# auto.net
KiCad netlist of a schematic drawn in EAGLE
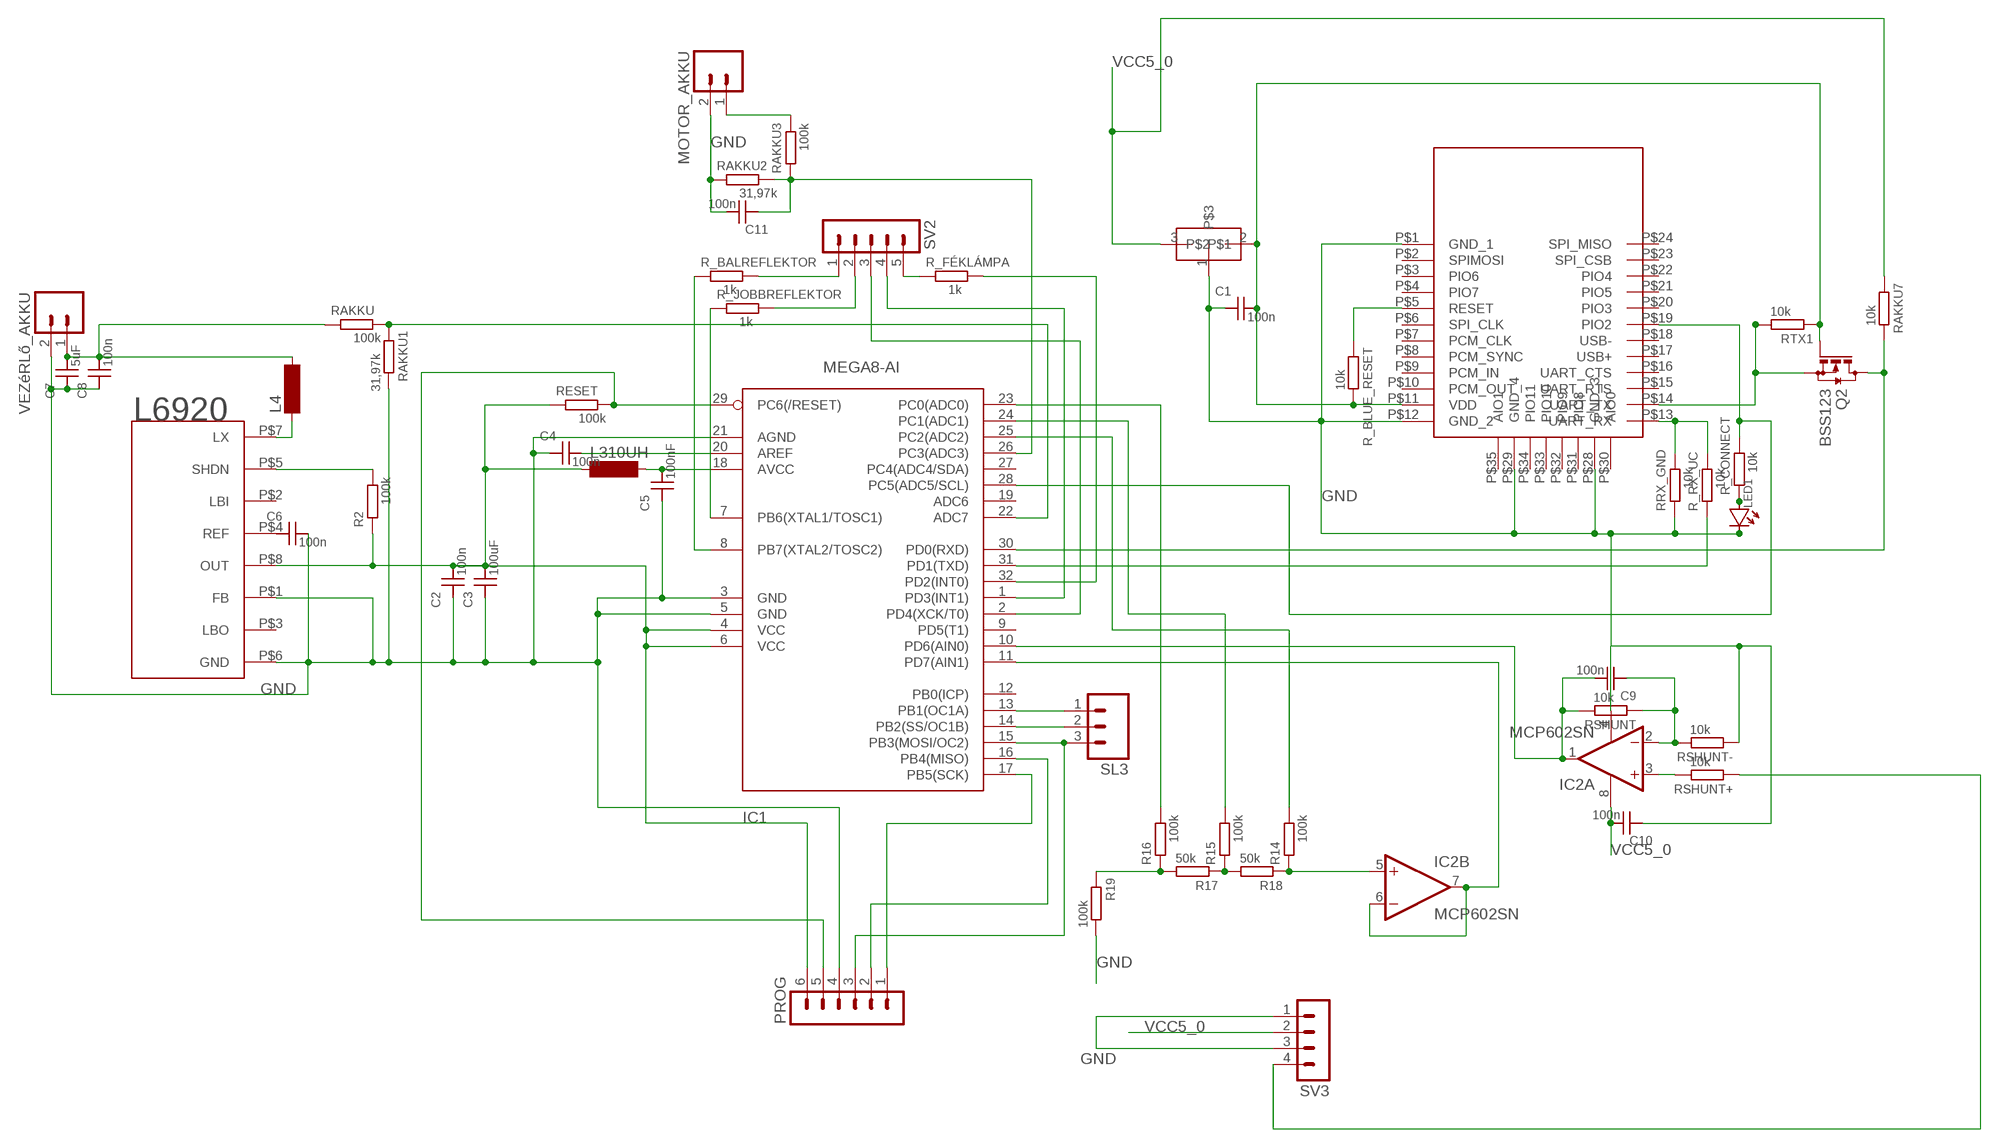
[diagram p0: schematic, sheet 1]

(export (version "E")
  (design (tool "Eeschema 10.0.6"))
  (components
    (comp (ref "C1")
      (value "100n")
      (footprint "eagle-import:1206")
      (libsource (lib "eagle-import") (part "C"))
    )
    (comp (ref "C2")
      (value "100n")
      (footprint "eagle-import:1206")
      (libsource (lib "eagle-import") (part "C"))
    )
    (comp (ref "C3")
      (value "100uF")
      (footprint "eagle-import:1206")
      (libsource (lib "eagle-import") (part "C"))
    )
    (comp (ref "C4")
      (value "100n")
      (footprint "eagle-import:1206")
      (libsource (lib "eagle-import") (part "C"))
    )
    (comp (ref "C5")
      (value "100nF")
      (footprint "eagle-import:1206")
      (libsource (lib "eagle-import") (part "C"))
    )
    (comp (ref "C6")
      (value "100n")
      (footprint "eagle-import:1206")
      (libsource (lib "eagle-import") (part "C"))
    )
    (comp (ref "C7")
      (value "5uF")
      (footprint "eagle-import:1206")
      (libsource (lib "eagle-import") (part "C"))
    )
    (comp (ref "C8")
      (value "100n")
      (footprint "eagle-import:1206")
      (libsource (lib "eagle-import") (part "C"))
    )
    (comp (ref "C9")
      (value "100n")
      (footprint "eagle-import:1206")
      (libsource (lib "eagle-import") (part "C"))
    )
    (comp (ref "C10")
      (value "100n")
      (footprint "eagle-import:1206")
      (libsource (lib "eagle-import") (part "C"))
    )
    (comp (ref "C11")
      (value "100n")
      (footprint "eagle-import:1206")
      (libsource (lib "eagle-import") (part "C"))
    )
    (comp (ref "IC1")
      (value "MEGA8-AI")
      (footprint "eagle-import:TQFP32-08")
      (libsource (lib "eagle-import") (part "MEGA8-AI"))
    )
    (comp (ref "IC2")
      (value "MCP602SN")
      (footprint "eagle-import:SO08")
      (libsource (lib "eagle-import") (part "MCP602SN"))
    )
    (comp (ref "L4")
      (value "SM-NE29")
      (footprint "eagle-import:SM-NE29")
      (libsource (lib "eagle-import") (part "SM-NE29"))
    )
    (comp (ref "L310UH")
      (value "SM-NE29")
      (footprint "eagle-import:SM-NE29")
      (libsource (lib "eagle-import") (part "SM-NE29"))
    )
    (comp (ref "LED1")
      (value "LED")
      (footprint "eagle-import:1206")
      (libsource (lib "eagle-import") (part "LED"))
    )
    (comp (ref "MCP1700-3302")
      (value "MCP1700-1802")
      (footprint "eagle-import:SOT23")
      (libsource (lib "eagle-import") (part "MCP1700-1802"))
    )
    (comp (ref "MOTOR_AKKU")
      (value "M02")
      (footprint "eagle-import:02P")
      (fields (field (name "OC_FARNELL") "unknown") (field (name "OC_NEWARK") "unknown"))
      (libsource (lib "eagle-import") (part "M02"))
    )
    (comp (ref "PROG")
      (value "MA06-1")
      (footprint "eagle-import:MA06-1")
      (libsource (lib "eagle-import") (part "MA06-1"))
    )
    (comp (ref "Q2")
      (value "BSS123")
      (footprint "eagle-import:SOT23")
      (libsource (lib "eagle-import") (part "transistor-small-signal_BSS123"))
    )
    (comp (ref "R2")
      (value "100k")
      (footprint "eagle-import:1206")
      (libsource (lib "eagle-import") (part "R"))
    )
    (comp (ref "R14")
      (value "100k")
      (footprint "eagle-import:1206")
      (libsource (lib "eagle-import") (part "R"))
    )
    (comp (ref "R15")
      (value "100k")
      (footprint "eagle-import:1206")
      (libsource (lib "eagle-import") (part "R"))
    )
    (comp (ref "R16")
      (value "100k")
      (footprint "eagle-import:1206")
      (libsource (lib "eagle-import") (part "R"))
    )
    (comp (ref "R17")
      (value "50k")
      (footprint "eagle-import:1206")
      (libsource (lib "eagle-import") (part "R"))
    )
    (comp (ref "R18")
      (value "50k")
      (footprint "eagle-import:1206")
      (libsource (lib "eagle-import") (part "R"))
    )
    (comp (ref "R19")
      (value "100k")
      (footprint "eagle-import:1206")
      (libsource (lib "eagle-import") (part "R"))
    )
    (comp (ref "RAKKU")
      (value "100k")
      (footprint "eagle-import:1206")
      (libsource (lib "eagle-import") (part "R"))
    )
    (comp (ref "RAKKU1")
      (value "31,97k")
      (footprint "eagle-import:1206")
      (libsource (lib "eagle-import") (part "R"))
    )
    (comp (ref "RAKKU2")
      (value "31,97k")
      (footprint "eagle-import:1206")
      (libsource (lib "eagle-import") (part "R"))
    )
    (comp (ref "RAKKU3")
      (value "100k")
      (footprint "eagle-import:1206")
      (libsource (lib "eagle-import") (part "R"))
    )
    (comp (ref "RAKKU7")
      (value "10k")
      (footprint "eagle-import:1206")
      (libsource (lib "eagle-import") (part "R"))
    )
    (comp (ref "RESET")
      (value "100k")
      (footprint "eagle-import:1206")
      (libsource (lib "eagle-import") (part "R"))
    )
    (comp (ref "RRX_GND")
      (value "10k")
      (footprint "eagle-import:1206")
      (libsource (lib "eagle-import") (part "R"))
    )
    (comp (ref "RSHUNT")
      (value "10k")
      (footprint "eagle-import:1206")
      (libsource (lib "eagle-import") (part "R"))
    )
    (comp (ref "RSHUNT+")
      (value "10k")
      (footprint "eagle-import:1206")
      (libsource (lib "eagle-import") (part "R"))
    )
    (comp (ref "RSHUNT-")
      (value "10k")
      (footprint "eagle-import:1206")
      (libsource (lib "eagle-import") (part "R"))
    )
    (comp (ref "RTX1")
      (value "10k")
      (footprint "eagle-import:1206")
      (libsource (lib "eagle-import") (part "R"))
    )
    (comp (ref "R_BALREFLEKTOR")
      (value "1k")
      (footprint "eagle-import:1206")
      (libsource (lib "eagle-import") (part "R"))
    )
    (comp (ref "R_BLUE_RESET")
      (value "10k")
      (footprint "eagle-import:1206")
      (libsource (lib "eagle-import") (part "R"))
    )
    (comp (ref "R_CONNECT")
      (value "10k")
      (footprint "eagle-import:1206")
      (libsource (lib "eagle-import") (part "R"))
    )
    (comp (ref "R_FÉKLÁMPA")
      (value "1k")
      (footprint "eagle-import:1206")
      (libsource (lib "eagle-import") (part "R"))
    )
    (comp (ref "R_JOBBREFLEKTOR")
      (value "1k")
      (footprint "eagle-import:1206")
      (libsource (lib "eagle-import") (part "R"))
    )
    (comp (ref "R_RX_UC")
      (value "10k")
      (footprint "eagle-import:1206")
      (libsource (lib "eagle-import") (part "R"))
    )
    (comp (ref "SL3")
      (value "MA03")
      (footprint "eagle-import:03P")
      (fields (field (name "OC_FARNELL") "unknown") (field (name "OC_NEWARK") "unknown"))
      (libsource (lib "eagle-import") (part "MA03"))
    )
    (comp (ref "SV2")
      (value "MA05-1")
      (footprint "eagle-import:MA05-1")
      (libsource (lib "eagle-import") (part "MA05-1"))
    )
    (comp (ref "SV3")
      (value "MA04-1")
      (footprint "eagle-import:MA04-1")
      (libsource (lib "eagle-import") (part "MA04-1"))
    )
    (comp (ref "U$1")
      (value "L6920")
      (footprint "eagle-import:L6920")
      (libsource (lib "eagle-import") (part "L6920"))
    )
    (comp (ref "U$7")
      (value "RN41")
      (footprint "eagle-import:RN41")
      (libsource (lib "eagle-import") (part "RN41"))
    )
    (comp (ref "VEZéRLő_AKKU")
      (value "M02")
      (footprint "eagle-import:02P")
      (libsource (lib "eagle-import") (part "M02"))
    )
  )
  (nets
    (net (code "1") (name "/GND") (class "Default")
      (node (ref "C1") (pin "PIN") (pinfunction "P$1_PIN") (pintype "passive"))
      (node (ref "C10") (pin "PIN") (pinfunction "P$1_PIN") (pintype "passive"))
      (node (ref "C11") (pin "PIN+") (pinfunction "P$2_PIN+") (pintype "passive"))
      (node (ref "C2") (pin "PIN") (pinfunction "P$1_PIN") (pintype "passive"))
      (node (ref "C3") (pin "PIN") (pinfunction "P$1_PIN") (pintype "passive"))
      (node (ref "C4") (pin "PIN") (pinfunction "P$1_PIN") (pintype "passive"))
      (node (ref "C5") (pin "PIN") (pinfunction "P$1_PIN") (pintype "passive"))
      (node (ref "C6") (pin "PIN+") (pinfunction "P$2_PIN+") (pintype "passive"))
      (node (ref "C7") (pin "PIN") (pinfunction "P$1_PIN") (pintype "passive"))
      (node (ref "C8") (pin "PIN") (pinfunction "P$1_PIN") (pintype "passive"))
      (node (ref "IC1") (pin "21") (pinfunction "AGND_21") (pintype "bidirectional"))
      (node (ref "IC1") (pin "3") (pinfunction "GND_3") (pintype "bidirectional"))
      (node (ref "IC1") (pin "5") (pinfunction "GND_5") (pintype "bidirectional"))
      (node (ref "IC2") (pin "4") (pinfunction "V-_4") (pintype "power_in"))
      (node (ref "LED1") (pin "PIN+") (pinfunction "L-_PIN+") (pintype "passive"))
      (node (ref "MCP1700-3302") (pin "1") (pinfunction "P$3_1") (pintype "bidirectional"))
      (node (ref "MOTOR_AKKU") (pin "1") (pinfunction "1_1") (pintype "passive"))
      (node (ref "MOTOR_AKKU") (pin "2") (pinfunction "2_2") (pintype "passive"))
      (node (ref "PROG") (pin "4") (pinfunction "4_4") (pintype "passive"))
      (node (ref "R19") (pin "PIN+") (pinfunction "P$2_PIN+") (pintype "passive"))
      (node (ref "RAKKU1") (pin "PIN+") (pinfunction "P$2_PIN+") (pintype "passive"))
      (node (ref "RAKKU2") (pin "PIN") (pinfunction "P$1_PIN") (pintype "passive"))
      (node (ref "RAKKU3") (pin "PIN+") (pinfunction "P$2_PIN+") (pintype "passive"))
      (node (ref "RRX_GND") (pin "PIN") (pinfunction "P$1_PIN") (pintype "passive"))
      (node (ref "RSHUNT-") (pin "PIN") (pinfunction "P$1_PIN") (pintype "passive"))
      (node (ref "SV3") (pin "1") (pinfunction "1_1") (pintype "passive"))
      (node (ref "SV3") (pin "3") (pinfunction "3_3") (pintype "passive"))
      (node (ref "U$1") (pin "P$1") (pinfunction "FB_P$1") (pintype "bidirectional"))
      (node (ref "U$1") (pin "P$6") (pinfunction "GND_P$6") (pintype "bidirectional"))
      (node (ref "U$7") (pin "P$1") (pinfunction "GND_1_P$1") (pintype "power_in"))
      (node (ref "U$7") (pin "P$12") (pinfunction "GND_2_P$12") (pintype "bidirectional"))
      (node (ref "U$7") (pin "P$28") (pinfunction "GND_3_P$28") (pintype "bidirectional"))
      (node (ref "U$7") (pin "P$29") (pinfunction "GND_4_P$29") (pintype "bidirectional"))
      (node (ref "VEZéRLő_AKKU") (pin "2") (pinfunction "2_2") (pintype "passive"))
    )
    (net (code "2") (name "/VCC5_0") (class "Default")
      (node (ref "C10") (pin "PIN+") (pinfunction "P$2_PIN+") (pintype "passive"))
      (node (ref "C2") (pin "PIN+") (pinfunction "P$2_PIN+") (pintype "passive"))
      (node (ref "C3") (pin "PIN+") (pinfunction "P$2_PIN+") (pintype "passive"))
      (node (ref "IC1") (pin "4") (pinfunction "VCC_4") (pintype "bidirectional"))
      (node (ref "IC1") (pin "6") (pinfunction "VCC_6") (pintype "bidirectional"))
      (node (ref "IC2") (pin "8") (pinfunction "V+_8") (pintype "power_in"))
      (node (ref "L310UH") (pin "1") (pinfunction "1_1") (pintype "passive"))
      (node (ref "MCP1700-3302") (pin "3") (pinfunction "P$1_3") (pintype "bidirectional"))
      (node (ref "PROG") (pin "6") (pinfunction "6_6") (pintype "passive"))
      (node (ref "R2") (pin "PIN") (pinfunction "P$1_PIN") (pintype "passive"))
      (node (ref "RAKKU7") (pin "PIN") (pinfunction "P$1_PIN") (pintype "passive"))
      (node (ref "RESET") (pin "PIN") (pinfunction "P$1_PIN") (pintype "passive"))
      (node (ref "SV3") (pin "2") (pinfunction "2_2") (pintype "passive"))
      (node (ref "U$1") (pin "P$8") (pinfunction "OUT_P$8") (pintype "bidirectional"))
    )
    (net (code "3") (name "Net-(C1-P$2)") (class "Default")
      (node (ref "C1") (pin "PIN+") (pinfunction "P$2_PIN+") (pintype "passive"))
      (node (ref "MCP1700-3302") (pin "2") (pinfunction "P$2_2") (pintype "bidirectional"))
      (node (ref "Q2") (pin "1") (pinfunction "G_1") (pintype "passive"))
      (node (ref "RTX1") (pin "PIN") (pinfunction "P$1_PIN") (pintype "passive"))
      (node (ref "R_BLUE_RESET") (pin "PIN+") (pinfunction "P$2_PIN+") (pintype "passive"))
      (node (ref "U$7") (pin "P$11") (pinfunction "VDD_P$11") (pintype "bidirectional"))
    )
    (net (code "4") (name "Net-(C4-P$2)") (class "Default")
      (node (ref "C4") (pin "PIN+") (pinfunction "P$2_PIN+") (pintype "passive"))
      (node (ref "IC1") (pin "20") (pinfunction "AREF_20") (pintype "bidirectional"))
    )
    (net (code "5") (name "Net-(C5-P$2)") (class "Default")
      (node (ref "C5") (pin "PIN+") (pinfunction "P$2_PIN+") (pintype "passive"))
      (node (ref "IC1") (pin "18") (pinfunction "AVCC_18") (pintype "bidirectional"))
      (node (ref "L310UH") (pin "2") (pinfunction "2_2") (pintype "passive"))
    )
    (net (code "6") (name "Net-(C6-P$1)") (class "Default")
      (node (ref "C6") (pin "PIN") (pinfunction "P$1_PIN") (pintype "passive"))
      (node (ref "U$1") (pin "P$4") (pinfunction "REF_P$4") (pintype "bidirectional"))
    )
    (net (code "7") (name "Net-(C7-P$2)") (class "Default")
      (node (ref "C7") (pin "PIN+") (pinfunction "P$2_PIN+") (pintype "passive"))
      (node (ref "C8") (pin "PIN+") (pinfunction "P$2_PIN+") (pintype "passive"))
      (node (ref "L4") (pin "2") (pinfunction "2_2") (pintype "passive"))
      (node (ref "RAKKU") (pin "PIN") (pinfunction "P$1_PIN") (pintype "passive"))
      (node (ref "VEZéRLő_AKKU") (pin "1") (pinfunction "1_1") (pintype "passive"))
    )
    (net (code "8") (name "Net-(C9-P$1)") (class "Default")
      (node (ref "C9") (pin "PIN") (pinfunction "P$1_PIN") (pintype "passive"))
      (node (ref "IC2") (pin "2") (pinfunction "-IN_2") (pintype "input"))
      (node (ref "RSHUNT") (pin "PIN") (pinfunction "P$1_PIN") (pintype "passive"))
      (node (ref "RSHUNT-") (pin "PIN+") (pinfunction "P$2_PIN+") (pintype "passive"))
    )
    (net (code "9") (name "Net-(C9-P$2)") (class "Default")
      (node (ref "C9") (pin "PIN+") (pinfunction "P$2_PIN+") (pintype "passive"))
      (node (ref "IC1") (pin "10") (pinfunction "PD6(AIN0)_10") (pintype "bidirectional"))
      (node (ref "IC2") (pin "1") (pinfunction "OUT_1") (pintype "output"))
      (node (ref "RSHUNT") (pin "PIN+") (pinfunction "P$2_PIN+") (pintype "passive"))
    )
    (net (code "10") (name "Net-(C11-P$1)") (class "Default")
      (node (ref "C11") (pin "PIN") (pinfunction "P$1_PIN") (pintype "passive"))
      (node (ref "IC1") (pin "26") (pinfunction "PC3(ADC3)_26") (pintype "bidirectional"))
      (node (ref "RAKKU2") (pin "PIN+") (pinfunction "P$2_PIN+") (pintype "passive"))
      (node (ref "RAKKU3") (pin "PIN") (pinfunction "P$1_PIN") (pintype "passive"))
    )
    (net (code "11") (name "Net-(IC1-ADC7)") (class "Default")
      (node (ref "IC1") (pin "22") (pinfunction "ADC7_22") (pintype "bidirectional"))
      (node (ref "RAKKU") (pin "PIN+") (pinfunction "P$2_PIN+") (pintype "passive"))
      (node (ref "RAKKU1") (pin "PIN") (pinfunction "P$1_PIN") (pintype "passive"))
    )
    (net (code "12") (name "Net-(IC1-PB1(OC1A))") (class "Default")
      (node (ref "IC1") (pin "13") (pinfunction "PB1(OC1A)_13") (pintype "bidirectional"))
      (node (ref "SL3") (pin "1") (pinfunction "1_1") (pintype "passive"))
    )
    (net (code "13") (name "Net-(IC1-PB2(SS{slash}OC1B))") (class "Default")
      (node (ref "IC1") (pin "14") (pinfunction "PB2(SS/OC1B)_14") (pintype "bidirectional"))
      (node (ref "SL3") (pin "2") (pinfunction "2_2") (pintype "passive"))
    )
    (net (code "14") (name "Net-(IC1-PB3(MOSI{slash}OC2))") (class "Default")
      (node (ref "IC1") (pin "15") (pinfunction "PB3(MOSI/OC2)_15") (pintype "bidirectional"))
      (node (ref "PROG") (pin "3") (pinfunction "3_3") (pintype "passive"))
      (node (ref "SL3") (pin "3") (pinfunction "3_3") (pintype "passive"))
    )
    (net (code "15") (name "Net-(IC1-PB4(MISO))") (class "Default")
      (node (ref "IC1") (pin "16") (pinfunction "PB4(MISO)_16") (pintype "bidirectional"))
      (node (ref "PROG") (pin "2") (pinfunction "2_2") (pintype "passive"))
    )
    (net (code "16") (name "Net-(IC1-PB5(SCK))") (class "Default")
      (node (ref "IC1") (pin "17") (pinfunction "PB5(SCK)_17") (pintype "bidirectional"))
      (node (ref "PROG") (pin "1") (pinfunction "1_1") (pintype "passive"))
    )
    (net (code "17") (name "Net-(IC1-PB6(XTAL1{slash}TOSC1))") (class "Default")
      (node (ref "IC1") (pin "7") (pinfunction "PB6(XTAL1/TOSC1)_7") (pintype "bidirectional"))
      (node (ref "R_JOBBREFLEKTOR") (pin "PIN") (pinfunction "P$1_PIN") (pintype "passive"))
    )
    (net (code "18") (name "Net-(IC1-PB7(XTAL2{slash}TOSC2))") (class "Default")
      (node (ref "IC1") (pin "8") (pinfunction "PB7(XTAL2/TOSC2)_8") (pintype "bidirectional"))
      (node (ref "R_BALREFLEKTOR") (pin "PIN") (pinfunction "P$1_PIN") (pintype "passive"))
    )
    (net (code "19") (name "Net-(IC1-PC0(ADC0))") (class "Default")
      (node (ref "IC1") (pin "23") (pinfunction "PC0(ADC0)_23") (pintype "bidirectional"))
      (node (ref "R16") (pin "PIN+") (pinfunction "P$2_PIN+") (pintype "passive"))
    )
    (net (code "20") (name "Net-(IC1-PC1(ADC1))") (class "Default")
      (node (ref "IC1") (pin "24") (pinfunction "PC1(ADC1)_24") (pintype "bidirectional"))
      (node (ref "R15") (pin "PIN+") (pinfunction "P$2_PIN+") (pintype "passive"))
    )
    (net (code "21") (name "Net-(IC1-PC2(ADC2))") (class "Default")
      (node (ref "IC1") (pin "25") (pinfunction "PC2(ADC2)_25") (pintype "bidirectional"))
      (node (ref "R14") (pin "PIN+") (pinfunction "P$2_PIN+") (pintype "passive"))
    )
    (net (code "22") (name "Net-(IC1-PC5(ADC5{slash}SCL))") (class "Default")
      (node (ref "IC1") (pin "28") (pinfunction "PC5(ADC5/SCL)_28") (pintype "bidirectional"))
      (node (ref "R_CONNECT") (pin "PIN+") (pinfunction "P$2_PIN+") (pintype "passive"))
      (node (ref "U$7") (pin "P$19") (pinfunction "PIO2_P$19") (pintype "bidirectional"))
    )
    (net (code "23") (name "Net-(IC1-PC6({slash}RESET))") (class "Default")
      (node (ref "IC1") (pin "29") (pinfunction "PC6(/RESET)_29") (pintype "bidirectional"))
      (node (ref "PROG") (pin "5") (pinfunction "5_5") (pintype "passive"))
      (node (ref "RESET") (pin "PIN+") (pinfunction "P$2_PIN+") (pintype "passive"))
    )
    (net (code "24") (name "Net-(IC1-PD0(RXD))") (class "Default")
      (node (ref "IC1") (pin "30") (pinfunction "PD0(RXD)_30") (pintype "bidirectional"))
      (node (ref "Q2") (pin "3") (pinfunction "D_3") (pintype "passive"))
      (node (ref "RAKKU7") (pin "PIN+") (pinfunction "P$2_PIN+") (pintype "passive"))
    )
    (net (code "25") (name "Net-(IC1-PD1(TXD))") (class "Default")
      (node (ref "IC1") (pin "31") (pinfunction "PD1(TXD)_31") (pintype "bidirectional"))
      (node (ref "R_RX_UC") (pin "PIN") (pinfunction "P$1_PIN") (pintype "passive"))
    )
    (net (code "26") (name "Net-(IC1-PD2(INT0))") (class "Default")
      (node (ref "IC1") (pin "32") (pinfunction "PD2(INT0)_32") (pintype "bidirectional"))
      (node (ref "R_FÉKLÁMPA") (pin "PIN+") (pinfunction "P$2_PIN+") (pintype "passive"))
    )
    (net (code "27") (name "Net-(IC1-PD3(INT1))") (class "Default")
      (node (ref "IC1") (pin "1") (pinfunction "PD3(INT1)_1") (pintype "bidirectional"))
      (node (ref "SV2") (pin "4") (pinfunction "4_4") (pintype "passive"))
    )
    (net (code "28") (name "Net-(IC1-PD4(XCK{slash}T0))") (class "Default")
      (node (ref "IC1") (pin "2") (pinfunction "PD4(XCK/T0)_2") (pintype "bidirectional"))
      (node (ref "SV2") (pin "3") (pinfunction "3_3") (pintype "passive"))
    )
    (net (code "29") (name "Net-(IC1-PD7(AIN1))") (class "Default")
      (node (ref "IC1") (pin "11") (pinfunction "PD7(AIN1)_11") (pintype "bidirectional"))
      (node (ref "IC2") (pin "6") (pinfunction "-IN_6") (pintype "input"))
      (node (ref "IC2") (pin "7") (pinfunction "OUT_7") (pintype "output"))
    )
    (net (code "30") (name "Net-(IC2A-+IN)") (class "Default")
      (node (ref "IC2") (pin "3") (pinfunction "+IN_3") (pintype "input"))
      (node (ref "RSHUNT+") (pin "PIN+") (pinfunction "P$2_PIN+") (pintype "passive"))
    )
    (net (code "31") (name "Net-(IC2B-+IN)") (class "Default")
      (node (ref "IC2") (pin "5") (pinfunction "+IN_5") (pintype "input"))
      (node (ref "R14") (pin "PIN") (pinfunction "P$1_PIN") (pintype "passive"))
      (node (ref "R18") (pin "PIN") (pinfunction "P$1_PIN") (pintype "passive"))
    )
    (net (code "32") (name "Net-(LED1-L+)") (class "Default")
      (node (ref "LED1") (pin "PIN") (pinfunction "L+_PIN") (pintype "passive"))
      (node (ref "R_CONNECT") (pin "PIN") (pinfunction "P$1_PIN") (pintype "passive"))
    )
    (net (code "33") (name "Net-(Q2-S)") (class "Default")
      (node (ref "Q2") (pin "2") (pinfunction "S_2") (pintype "passive"))
      (node (ref "RTX1") (pin "PIN+") (pinfunction "P$2_PIN+") (pintype "passive"))
      (node (ref "U$7") (pin "P$14") (pinfunction "UART_TX_P$14") (pintype "bidirectional"))
    )
    (net (code "34") (name "Net-(R2-P$2)") (class "Default")
      (node (ref "R2") (pin "PIN+") (pinfunction "P$2_PIN+") (pintype "passive"))
      (node (ref "U$1") (pin "P$5") (pinfunction "SHDN_P$5") (pintype "bidirectional"))
    )
    (net (code "35") (name "Net-(R15-P$1)") (class "Default")
      (node (ref "R15") (pin "PIN") (pinfunction "P$1_PIN") (pintype "passive"))
      (node (ref "R17") (pin "PIN") (pinfunction "P$1_PIN") (pintype "passive"))
      (node (ref "R18") (pin "PIN+") (pinfunction "P$2_PIN+") (pintype "passive"))
    )
    (net (code "36") (name "Net-(R16-P$1)") (class "Default")
      (node (ref "R16") (pin "PIN") (pinfunction "P$1_PIN") (pintype "passive"))
      (node (ref "R17") (pin "PIN+") (pinfunction "P$2_PIN+") (pintype "passive"))
      (node (ref "R19") (pin "PIN") (pinfunction "P$1_PIN") (pintype "passive"))
    )
    (net (code "37") (name "Net-(RRX_GND-P$2)") (class "Default")
      (node (ref "RRX_GND") (pin "PIN+") (pinfunction "P$2_PIN+") (pintype "passive"))
      (node (ref "R_RX_UC") (pin "PIN+") (pinfunction "P$2_PIN+") (pintype "passive"))
      (node (ref "U$7") (pin "P$13") (pinfunction "UART_RX_P$13") (pintype "bidirectional"))
    )
    (net (code "38") (name "Net-(RSHUNT+-P$1)") (class "Default")
      (node (ref "RSHUNT+") (pin "PIN") (pinfunction "P$1_PIN") (pintype "passive"))
      (node (ref "SV3") (pin "4") (pinfunction "4_4") (pintype "passive"))
    )
    (net (code "39") (name "Net-(R_BALREFLEKTOR-P$2)") (class "Default")
      (node (ref "R_BALREFLEKTOR") (pin "PIN+") (pinfunction "P$2_PIN+") (pintype "passive"))
      (node (ref "SV2") (pin "1") (pinfunction "1_1") (pintype "passive"))
    )
    (net (code "40") (name "Net-(R_BLUE_RESET-P$1)") (class "Default")
      (node (ref "R_BLUE_RESET") (pin "PIN") (pinfunction "P$1_PIN") (pintype "passive"))
      (node (ref "U$7") (pin "P$5") (pinfunction "RESET_P$5") (pintype "bidirectional"))
    )
    (net (code "41") (name "Net-(R_FÉKLÁMPA-P$1)") (class "Default")
      (node (ref "R_FÉKLÁMPA") (pin "PIN") (pinfunction "P$1_PIN") (pintype "passive"))
      (node (ref "SV2") (pin "5") (pinfunction "5_5") (pintype "passive"))
    )
    (net (code "42") (name "Net-(R_JOBBREFLEKTOR-P$2)") (class "Default")
      (node (ref "R_JOBBREFLEKTOR") (pin "PIN+") (pinfunction "P$2_PIN+") (pintype "passive"))
      (node (ref "SV2") (pin "2") (pinfunction "2_2") (pintype "passive"))
    )
    (net (code "43") (name "Net-(U$1-LX)") (class "Default")
      (node (ref "L4") (pin "1") (pinfunction "1_1") (pintype "passive"))
      (node (ref "U$1") (pin "P$7") (pinfunction "LX_P$7") (pintype "bidirectional"))
    )
    (net (code "44") (name "unconnected-(IC1-ADC6-Pad19)") (class "Default")
      (node (ref "IC1") (pin "19") (pinfunction "ADC6_19") (pintype "bidirectional"))
    )
    (net (code "45") (name "unconnected-(IC1-PB0(ICP)-Pad12)") (class "Default")
      (node (ref "IC1") (pin "12") (pinfunction "PB0(ICP)_12") (pintype "bidirectional"))
    )
    (net (code "46") (name "unconnected-(IC1-PC4(ADC4{slash}SDA)-Pad27)") (class "Default")
      (node (ref "IC1") (pin "27") (pinfunction "PC4(ADC4/SDA)_27") (pintype "bidirectional"))
    )
    (net (code "47") (name "unconnected-(IC1-PD5(T1)-Pad9)") (class "Default")
      (node (ref "IC1") (pin "9") (pinfunction "PD5(T1)_9") (pintype "bidirectional"))
    )
    (net (code "48") (name "unconnected-(U$1-LBI-PadP$2)") (class "Default")
      (node (ref "U$1") (pin "P$2") (pinfunction "LBI_P$2") (pintype "bidirectional"))
    )
    (net (code "49") (name "unconnected-(U$1-LBO-PadP$3)") (class "Default")
      (node (ref "U$1") (pin "P$3") (pinfunction "LBO_P$3") (pintype "bidirectional"))
    )
    (net (code "50") (name "unconnected-(U$7-AIO0-PadP$30)") (class "Default")
      (node (ref "U$7") (pin "P$30") (pinfunction "AIO0_P$30") (pintype "bidirectional"))
    )
    (net (code "51") (name "unconnected-(U$7-AIO1-PadP$35)") (class "Default")
      (node (ref "U$7") (pin "P$35") (pinfunction "AIO1_P$35") (pintype "bidirectional"))
    )
    (net (code "52") (name "unconnected-(U$7-PCM_CLK-PadP$7)") (class "Default")
      (node (ref "U$7") (pin "P$7") (pinfunction "PCM_CLK_P$7") (pintype "bidirectional"))
    )
    (net (code "53") (name "unconnected-(U$7-PCM_IN-PadP$9)") (class "Default")
      (node (ref "U$7") (pin "P$9") (pinfunction "PCM_IN_P$9") (pintype "bidirectional"))
    )
    (net (code "54") (name "unconnected-(U$7-PCM_OUT-PadP$10)") (class "Default")
      (node (ref "U$7") (pin "P$10") (pinfunction "PCM_OUT_P$10") (pintype "bidirectional"))
    )
    (net (code "55") (name "unconnected-(U$7-PCM_SYNC-PadP$8)") (class "Default")
      (node (ref "U$7") (pin "P$8") (pinfunction "PCM_SYNC_P$8") (pintype "bidirectional"))
    )
    (net (code "56") (name "unconnected-(U$7-PIO3-PadP$20)") (class "Default")
      (node (ref "U$7") (pin "P$20") (pinfunction "PIO3_P$20") (pintype "bidirectional"))
    )
    (net (code "57") (name "unconnected-(U$7-PIO4-PadP$22)") (class "Default")
      (node (ref "U$7") (pin "P$22") (pinfunction "PIO4_P$22") (pintype "bidirectional"))
    )
    (net (code "58") (name "unconnected-(U$7-PIO5-PadP$21)") (class "Default")
      (node (ref "U$7") (pin "P$21") (pinfunction "PIO5_P$21") (pintype "bidirectional"))
    )
    (net (code "59") (name "unconnected-(U$7-PIO6-PadP$3)") (class "Default")
      (node (ref "U$7") (pin "P$3") (pinfunction "PIO6_P$3") (pintype "bidirectional"))
    )
    (net (code "60") (name "unconnected-(U$7-PIO7-PadP$4)") (class "Default")
      (node (ref "U$7") (pin "P$4") (pinfunction "PIO7_P$4") (pintype "bidirectional"))
    )
    (net (code "61") (name "unconnected-(U$7-PIO8-PadP$31)") (class "Default")
      (node (ref "U$7") (pin "P$31") (pinfunction "PIO8_P$31") (pintype "bidirectional"))
    )
    (net (code "62") (name "unconnected-(U$7-PIO9-PadP$32)") (class "Default")
      (node (ref "U$7") (pin "P$32") (pinfunction "PIO9_P$32") (pintype "bidirectional"))
    )
    (net (code "63") (name "unconnected-(U$7-PIO10-PadP$33)") (class "Default")
      (node (ref "U$7") (pin "P$33") (pinfunction "PIO10_P$33") (pintype "bidirectional"))
    )
    (net (code "64") (name "unconnected-(U$7-PIO11-PadP$34)") (class "Default")
      (node (ref "U$7") (pin "P$34") (pinfunction "PIO11_P$34") (pintype "bidirectional"))
    )
    (net (code "65") (name "unconnected-(U$7-SPIMOSI-PadP$2)") (class "Default")
      (node (ref "U$7") (pin "P$2") (pinfunction "SPIMOSI_P$2") (pintype "bidirectional"))
    )
    (net (code "66") (name "unconnected-(U$7-SPI_CLK-PadP$6)") (class "Default")
      (node (ref "U$7") (pin "P$6") (pinfunction "SPI_CLK_P$6") (pintype "bidirectional"))
    )
    (net (code "67") (name "unconnected-(U$7-SPI_CSB-PadP$23)") (class "Default")
      (node (ref "U$7") (pin "P$23") (pinfunction "SPI_CSB_P$23") (pintype "bidirectional"))
    )
    (net (code "68") (name "unconnected-(U$7-SPI_MISO-PadP$24)") (class "Default")
      (node (ref "U$7") (pin "P$24") (pinfunction "SPI_MISO_P$24") (pintype "bidirectional"))
    )
    (net (code "69") (name "unconnected-(U$7-UART_CTS-PadP$16)") (class "Default")
      (node (ref "U$7") (pin "P$16") (pinfunction "UART_CTS_P$16") (pintype "bidirectional"))
    )
    (net (code "70") (name "unconnected-(U$7-UART_RTS-PadP$15)") (class "Default")
      (node (ref "U$7") (pin "P$15") (pinfunction "UART_RTS_P$15") (pintype "bidirectional"))
    )
    (net (code "71") (name "unconnected-(U$7-USB+-PadP$17)") (class "Default")
      (node (ref "U$7") (pin "P$17") (pinfunction "USB+_P$17") (pintype "bidirectional"))
    )
    (net (code "72") (name "unconnected-(U$7-USB--PadP$18)") (class "Default")
      (node (ref "U$7") (pin "P$18") (pinfunction "USB-_P$18") (pintype "bidirectional"))
    )
  )
)
